# Omnetics_resistor_phantom.net
KiCad netlist of a schematic drawn in EAGLE
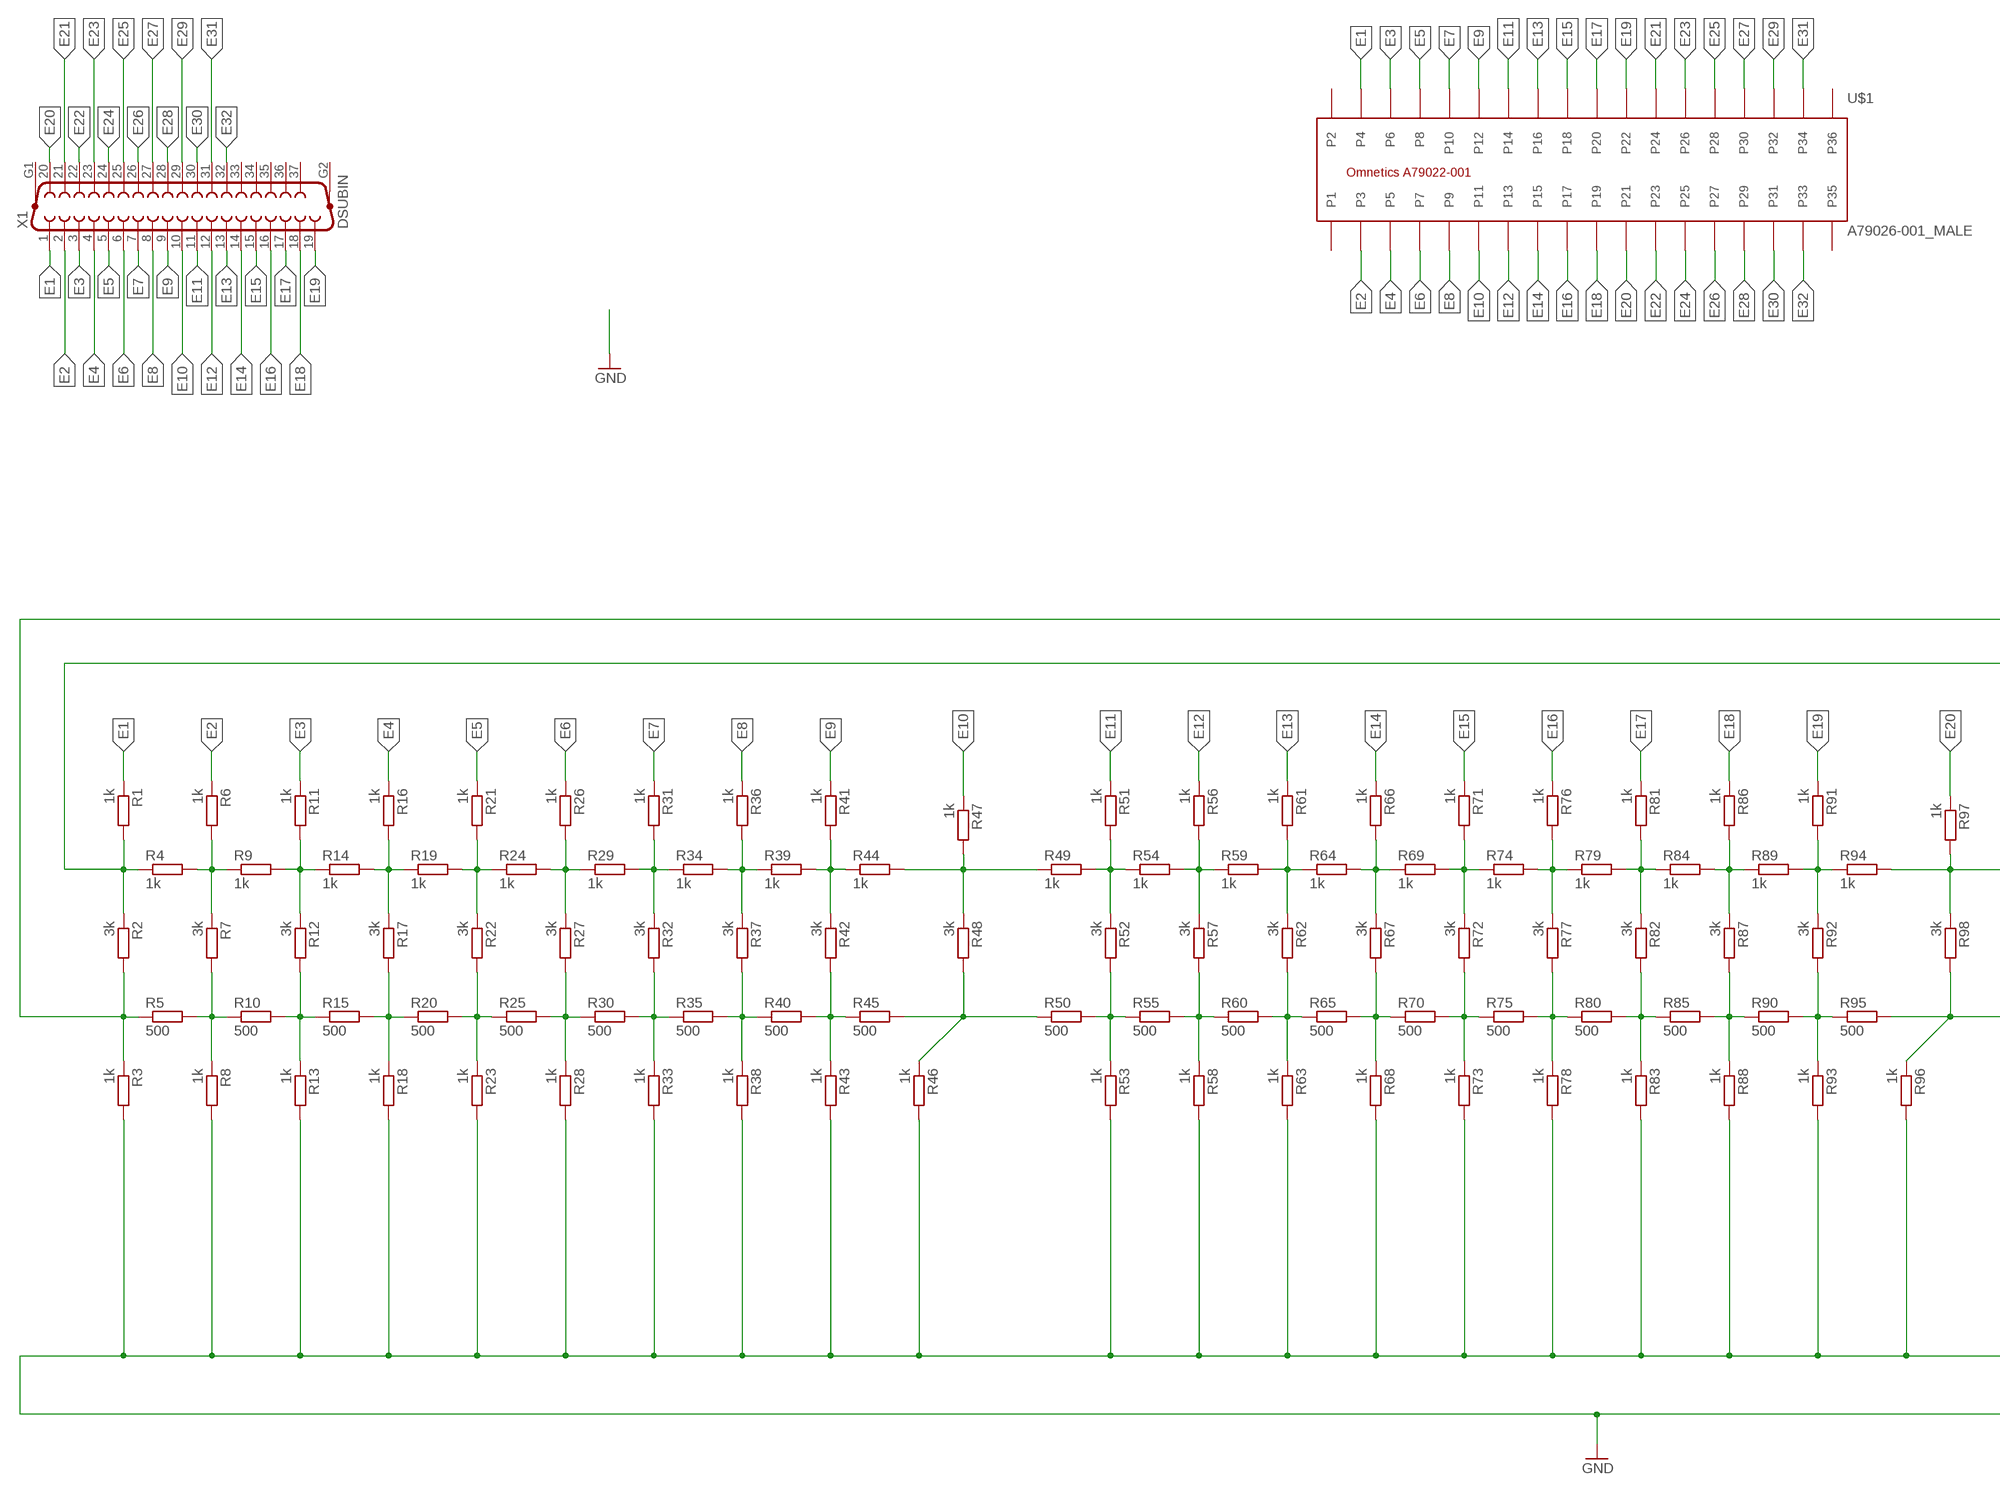
[diagram p0: schematic, sheet 1, part 1 of 2]
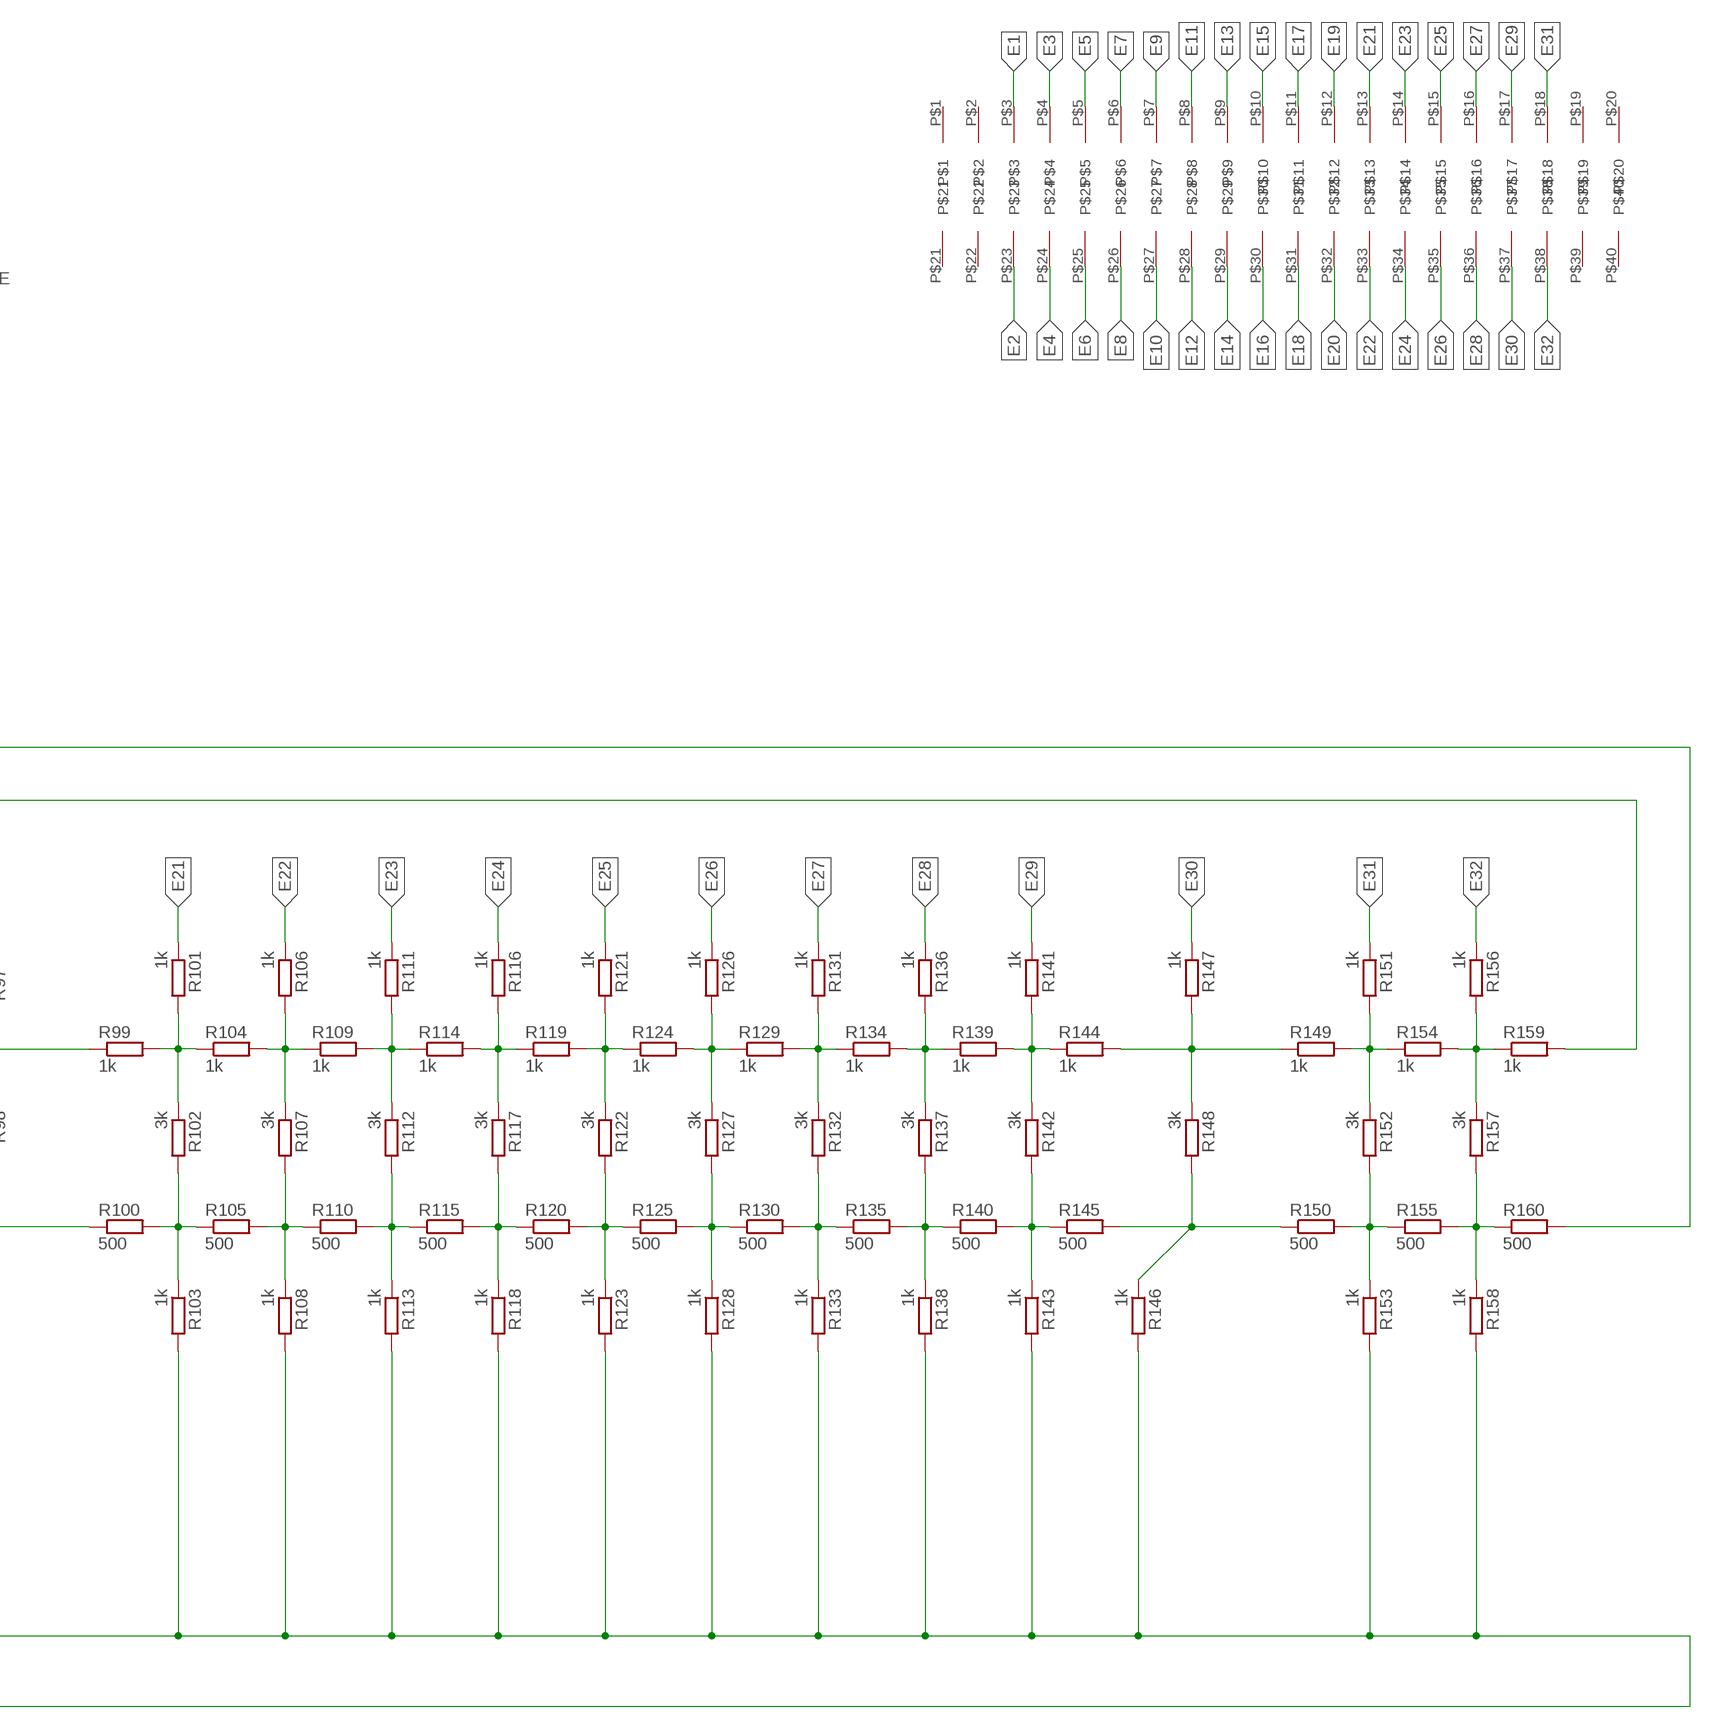
[diagram p1: schematic, sheet 1, part 2 of 2]

(export (version "E")
  (design (tool "Eeschema 10.0.6"))
  (components
    (comp (ref "R1")
      (value "1k")
      (footprint "eagle-import:R0402")
      (libsource (lib "eagle-import") (part "R-EU_R0402"))
    )
    (comp (ref "R2")
      (value "3k")
      (footprint "eagle-import:R0402")
      (libsource (lib "eagle-import") (part "R-EU_R0402"))
    )
    (comp (ref "R3")
      (value "1k")
      (footprint "eagle-import:R0402")
      (libsource (lib "eagle-import") (part "R-EU_R0402"))
    )
    (comp (ref "R4")
      (value "1k")
      (footprint "eagle-import:R0402")
      (libsource (lib "eagle-import") (part "R-EU_R0402"))
    )
    (comp (ref "R5")
      (value "500")
      (footprint "eagle-import:R0402")
      (libsource (lib "eagle-import") (part "R-EU_R0402"))
    )
    (comp (ref "R6")
      (value "1k")
      (footprint "eagle-import:R0402")
      (libsource (lib "eagle-import") (part "R-EU_R0402"))
    )
    (comp (ref "R7")
      (value "3k")
      (footprint "eagle-import:R0402")
      (libsource (lib "eagle-import") (part "R-EU_R0402"))
    )
    (comp (ref "R8")
      (value "1k")
      (footprint "eagle-import:R0402")
      (libsource (lib "eagle-import") (part "R-EU_R0402"))
    )
    (comp (ref "R9")
      (value "1k")
      (footprint "eagle-import:R0402")
      (libsource (lib "eagle-import") (part "R-EU_R0402"))
    )
    (comp (ref "R10")
      (value "500")
      (footprint "eagle-import:R0402")
      (libsource (lib "eagle-import") (part "R-EU_R0402"))
    )
    (comp (ref "R11")
      (value "1k")
      (footprint "eagle-import:R0402")
      (libsource (lib "eagle-import") (part "R-EU_R0402"))
    )
    (comp (ref "R12")
      (value "3k")
      (footprint "eagle-import:R0402")
      (libsource (lib "eagle-import") (part "R-EU_R0402"))
    )
    (comp (ref "R13")
      (value "1k")
      (footprint "eagle-import:R0402")
      (libsource (lib "eagle-import") (part "R-EU_R0402"))
    )
    (comp (ref "R14")
      (value "1k")
      (footprint "eagle-import:R0402")
      (libsource (lib "eagle-import") (part "R-EU_R0402"))
    )
    (comp (ref "R15")
      (value "500")
      (footprint "eagle-import:R0402")
      (libsource (lib "eagle-import") (part "R-EU_R0402"))
    )
    (comp (ref "R16")
      (value "1k")
      (footprint "eagle-import:R0402")
      (libsource (lib "eagle-import") (part "R-EU_R0402"))
    )
    (comp (ref "R17")
      (value "3k")
      (footprint "eagle-import:R0402")
      (libsource (lib "eagle-import") (part "R-EU_R0402"))
    )
    (comp (ref "R18")
      (value "1k")
      (footprint "eagle-import:R0402")
      (libsource (lib "eagle-import") (part "R-EU_R0402"))
    )
    (comp (ref "R19")
      (value "1k")
      (footprint "eagle-import:R0402")
      (libsource (lib "eagle-import") (part "R-EU_R0402"))
    )
    (comp (ref "R20")
      (value "500")
      (footprint "eagle-import:R0402")
      (libsource (lib "eagle-import") (part "R-EU_R0402"))
    )
    (comp (ref "R21")
      (value "1k")
      (footprint "eagle-import:R0402")
      (libsource (lib "eagle-import") (part "R-EU_R0402"))
    )
    (comp (ref "R22")
      (value "3k")
      (footprint "eagle-import:R0402")
      (libsource (lib "eagle-import") (part "R-EU_R0402"))
    )
    (comp (ref "R23")
      (value "1k")
      (footprint "eagle-import:R0402")
      (libsource (lib "eagle-import") (part "R-EU_R0402"))
    )
    (comp (ref "R24")
      (value "1k")
      (footprint "eagle-import:R0402")
      (libsource (lib "eagle-import") (part "R-EU_R0402"))
    )
    (comp (ref "R25")
      (value "500")
      (footprint "eagle-import:R0402")
      (libsource (lib "eagle-import") (part "R-EU_R0402"))
    )
    (comp (ref "R26")
      (value "1k")
      (footprint "eagle-import:R0402")
      (libsource (lib "eagle-import") (part "R-EU_R0402"))
    )
    (comp (ref "R27")
      (value "3k")
      (footprint "eagle-import:R0402")
      (libsource (lib "eagle-import") (part "R-EU_R0402"))
    )
    (comp (ref "R28")
      (value "1k")
      (footprint "eagle-import:R0402")
      (libsource (lib "eagle-import") (part "R-EU_R0402"))
    )
    (comp (ref "R29")
      (value "1k")
      (footprint "eagle-import:R0402")
      (libsource (lib "eagle-import") (part "R-EU_R0402"))
    )
    (comp (ref "R30")
      (value "500")
      (footprint "eagle-import:R0402")
      (libsource (lib "eagle-import") (part "R-EU_R0402"))
    )
    (comp (ref "R31")
      (value "1k")
      (footprint "eagle-import:R0402")
      (libsource (lib "eagle-import") (part "R-EU_R0402"))
    )
    (comp (ref "R32")
      (value "3k")
      (footprint "eagle-import:R0402")
      (libsource (lib "eagle-import") (part "R-EU_R0402"))
    )
    (comp (ref "R33")
      (value "1k")
      (footprint "eagle-import:R0402")
      (libsource (lib "eagle-import") (part "R-EU_R0402"))
    )
    (comp (ref "R34")
      (value "1k")
      (footprint "eagle-import:R0402")
      (libsource (lib "eagle-import") (part "R-EU_R0402"))
    )
    (comp (ref "R35")
      (value "500")
      (footprint "eagle-import:R0402")
      (libsource (lib "eagle-import") (part "R-EU_R0402"))
    )
    (comp (ref "R36")
      (value "1k")
      (footprint "eagle-import:R0402")
      (libsource (lib "eagle-import") (part "R-EU_R0402"))
    )
    (comp (ref "R37")
      (value "3k")
      (footprint "eagle-import:R0402")
      (libsource (lib "eagle-import") (part "R-EU_R0402"))
    )
    (comp (ref "R38")
      (value "1k")
      (footprint "eagle-import:R0402")
      (libsource (lib "eagle-import") (part "R-EU_R0402"))
    )
    (comp (ref "R39")
      (value "1k")
      (footprint "eagle-import:R0402")
      (libsource (lib "eagle-import") (part "R-EU_R0402"))
    )
    (comp (ref "R40")
      (value "500")
      (footprint "eagle-import:R0402")
      (libsource (lib "eagle-import") (part "R-EU_R0402"))
    )
    (comp (ref "R41")
      (value "1k")
      (footprint "eagle-import:R0402")
      (libsource (lib "eagle-import") (part "R-EU_R0402"))
    )
    (comp (ref "R42")
      (value "3k")
      (footprint "eagle-import:R0402")
      (libsource (lib "eagle-import") (part "R-EU_R0402"))
    )
    (comp (ref "R43")
      (value "1k")
      (footprint "eagle-import:R0402")
      (libsource (lib "eagle-import") (part "R-EU_R0402"))
    )
    (comp (ref "R44")
      (value "1k")
      (footprint "eagle-import:R0402")
      (libsource (lib "eagle-import") (part "R-EU_R0402"))
    )
    (comp (ref "R45")
      (value "500")
      (footprint "eagle-import:R0402")
      (libsource (lib "eagle-import") (part "R-EU_R0402"))
    )
    (comp (ref "R46")
      (value "1k")
      (footprint "eagle-import:R0402")
      (libsource (lib "eagle-import") (part "R-EU_R0402"))
    )
    (comp (ref "R47")
      (value "1k")
      (footprint "eagle-import:R0402")
      (libsource (lib "eagle-import") (part "R-EU_R0402"))
    )
    (comp (ref "R48")
      (value "3k")
      (footprint "eagle-import:R0402")
      (libsource (lib "eagle-import") (part "R-EU_R0402"))
    )
    (comp (ref "R49")
      (value "1k")
      (footprint "eagle-import:R0402")
      (libsource (lib "eagle-import") (part "R-EU_R0402"))
    )
    (comp (ref "R50")
      (value "500")
      (footprint "eagle-import:R0402")
      (libsource (lib "eagle-import") (part "R-EU_R0402"))
    )
    (comp (ref "R51")
      (value "1k")
      (footprint "eagle-import:R0402")
      (libsource (lib "eagle-import") (part "R-EU_R0402"))
    )
    (comp (ref "R52")
      (value "3k")
      (footprint "eagle-import:R0402")
      (libsource (lib "eagle-import") (part "R-EU_R0402"))
    )
    (comp (ref "R53")
      (value "1k")
      (footprint "eagle-import:R0402")
      (libsource (lib "eagle-import") (part "R-EU_R0402"))
    )
    (comp (ref "R54")
      (value "1k")
      (footprint "eagle-import:R0402")
      (libsource (lib "eagle-import") (part "R-EU_R0402"))
    )
    (comp (ref "R55")
      (value "500")
      (footprint "eagle-import:R0402")
      (libsource (lib "eagle-import") (part "R-EU_R0402"))
    )
    (comp (ref "R56")
      (value "1k")
      (footprint "eagle-import:R0402")
      (libsource (lib "eagle-import") (part "R-EU_R0402"))
    )
    (comp (ref "R57")
      (value "3k")
      (footprint "eagle-import:R0402")
      (libsource (lib "eagle-import") (part "R-EU_R0402"))
    )
    (comp (ref "R58")
      (value "1k")
      (footprint "eagle-import:R0402")
      (libsource (lib "eagle-import") (part "R-EU_R0402"))
    )
    (comp (ref "R59")
      (value "1k")
      (footprint "eagle-import:R0402")
      (libsource (lib "eagle-import") (part "R-EU_R0402"))
    )
    (comp (ref "R60")
      (value "500")
      (footprint "eagle-import:R0402")
      (libsource (lib "eagle-import") (part "R-EU_R0402"))
    )
    (comp (ref "R61")
      (value "1k")
      (footprint "eagle-import:R0402")
      (libsource (lib "eagle-import") (part "R-EU_R0402"))
    )
    (comp (ref "R62")
      (value "3k")
      (footprint "eagle-import:R0402")
      (libsource (lib "eagle-import") (part "R-EU_R0402"))
    )
    (comp (ref "R63")
      (value "1k")
      (footprint "eagle-import:R0402")
      (libsource (lib "eagle-import") (part "R-EU_R0402"))
    )
    (comp (ref "R64")
      (value "1k")
      (footprint "eagle-import:R0402")
      (libsource (lib "eagle-import") (part "R-EU_R0402"))
    )
    (comp (ref "R65")
      (value "500")
      (footprint "eagle-import:R0402")
      (libsource (lib "eagle-import") (part "R-EU_R0402"))
    )
    (comp (ref "R66")
      (value "1k")
      (footprint "eagle-import:R0402")
      (libsource (lib "eagle-import") (part "R-EU_R0402"))
    )
    (comp (ref "R67")
      (value "3k")
      (footprint "eagle-import:R0402")
      (libsource (lib "eagle-import") (part "R-EU_R0402"))
    )
    (comp (ref "R68")
      (value "1k")
      (footprint "eagle-import:R0402")
      (libsource (lib "eagle-import") (part "R-EU_R0402"))
    )
    (comp (ref "R69")
      (value "1k")
      (footprint "eagle-import:R0402")
      (libsource (lib "eagle-import") (part "R-EU_R0402"))
    )
    (comp (ref "R70")
      (value "500")
      (footprint "eagle-import:R0402")
      (libsource (lib "eagle-import") (part "R-EU_R0402"))
    )
    (comp (ref "R71")
      (value "1k")
      (footprint "eagle-import:R0402")
      (libsource (lib "eagle-import") (part "R-EU_R0402"))
    )
    (comp (ref "R72")
      (value "3k")
      (footprint "eagle-import:R0402")
      (libsource (lib "eagle-import") (part "R-EU_R0402"))
    )
    (comp (ref "R73")
      (value "1k")
      (footprint "eagle-import:R0402")
      (libsource (lib "eagle-import") (part "R-EU_R0402"))
    )
    (comp (ref "R74")
      (value "1k")
      (footprint "eagle-import:R0402")
      (libsource (lib "eagle-import") (part "R-EU_R0402"))
    )
    (comp (ref "R75")
      (value "500")
      (footprint "eagle-import:R0402")
      (libsource (lib "eagle-import") (part "R-EU_R0402"))
    )
    (comp (ref "R76")
      (value "1k")
      (footprint "eagle-import:R0402")
      (libsource (lib "eagle-import") (part "R-EU_R0402"))
    )
    (comp (ref "R77")
      (value "3k")
      (footprint "eagle-import:R0402")
      (libsource (lib "eagle-import") (part "R-EU_R0402"))
    )
    (comp (ref "R78")
      (value "1k")
      (footprint "eagle-import:R0402")
      (libsource (lib "eagle-import") (part "R-EU_R0402"))
    )
    (comp (ref "R79")
      (value "1k")
      (footprint "eagle-import:R0402")
      (libsource (lib "eagle-import") (part "R-EU_R0402"))
    )
    (comp (ref "R80")
      (value "500")
      (footprint "eagle-import:R0402")
      (libsource (lib "eagle-import") (part "R-EU_R0402"))
    )
    (comp (ref "R81")
      (value "1k")
      (footprint "eagle-import:R0402")
      (libsource (lib "eagle-import") (part "R-EU_R0402"))
    )
    (comp (ref "R82")
      (value "3k")
      (footprint "eagle-import:R0402")
      (libsource (lib "eagle-import") (part "R-EU_R0402"))
    )
    (comp (ref "R83")
      (value "1k")
      (footprint "eagle-import:R0402")
      (libsource (lib "eagle-import") (part "R-EU_R0402"))
    )
    (comp (ref "R84")
      (value "1k")
      (footprint "eagle-import:R0402")
      (libsource (lib "eagle-import") (part "R-EU_R0402"))
    )
    (comp (ref "R85")
      (value "500")
      (footprint "eagle-import:R0402")
      (libsource (lib "eagle-import") (part "R-EU_R0402"))
    )
    (comp (ref "R86")
      (value "1k")
      (footprint "eagle-import:R0402")
      (libsource (lib "eagle-import") (part "R-EU_R0402"))
    )
    (comp (ref "R87")
      (value "3k")
      (footprint "eagle-import:R0402")
      (libsource (lib "eagle-import") (part "R-EU_R0402"))
    )
    (comp (ref "R88")
      (value "1k")
      (footprint "eagle-import:R0402")
      (libsource (lib "eagle-import") (part "R-EU_R0402"))
    )
    (comp (ref "R89")
      (value "1k")
      (footprint "eagle-import:R0402")
      (libsource (lib "eagle-import") (part "R-EU_R0402"))
    )
    (comp (ref "R90")
      (value "500")
      (footprint "eagle-import:R0402")
      (libsource (lib "eagle-import") (part "R-EU_R0402"))
    )
    (comp (ref "R91")
      (value "1k")
      (footprint "eagle-import:R0402")
      (libsource (lib "eagle-import") (part "R-EU_R0402"))
    )
    (comp (ref "R92")
      (value "3k")
      (footprint "eagle-import:R0402")
      (libsource (lib "eagle-import") (part "R-EU_R0402"))
    )
    (comp (ref "R93")
      (value "1k")
      (footprint "eagle-import:R0402")
      (libsource (lib "eagle-import") (part "R-EU_R0402"))
    )
    (comp (ref "R94")
      (value "1k")
      (footprint "eagle-import:R0402")
      (libsource (lib "eagle-import") (part "R-EU_R0402"))
    )
    (comp (ref "R95")
      (value "500")
      (footprint "eagle-import:R0402")
      (libsource (lib "eagle-import") (part "R-EU_R0402"))
    )
    (comp (ref "R96")
      (value "1k")
      (footprint "eagle-import:R0402")
      (libsource (lib "eagle-import") (part "R-EU_R0402"))
    )
    (comp (ref "R97")
      (value "1k")
      (footprint "eagle-import:R0402")
      (libsource (lib "eagle-import") (part "R-EU_R0402"))
    )
    (comp (ref "R98")
      (value "3k")
      (footprint "eagle-import:R0402")
      (libsource (lib "eagle-import") (part "R-EU_R0402"))
    )
    (comp (ref "R99")
      (value "1k")
      (footprint "eagle-import:R0402")
      (libsource (lib "eagle-import") (part "R-EU_R0402"))
    )
    (comp (ref "R100")
      (value "500")
      (footprint "eagle-import:R0402")
      (libsource (lib "eagle-import") (part "R-EU_R0402"))
    )
    (comp (ref "R101")
      (value "1k")
      (footprint "eagle-import:R0402")
      (libsource (lib "eagle-import") (part "R-EU_R0402"))
    )
    (comp (ref "R102")
      (value "3k")
      (footprint "eagle-import:R0402")
      (libsource (lib "eagle-import") (part "R-EU_R0402"))
    )
    (comp (ref "R103")
      (value "1k")
      (footprint "eagle-import:R0402")
      (libsource (lib "eagle-import") (part "R-EU_R0402"))
    )
    (comp (ref "R104")
      (value "1k")
      (footprint "eagle-import:R0402")
      (libsource (lib "eagle-import") (part "R-EU_R0402"))
    )
    (comp (ref "R105")
      (value "500")
      (footprint "eagle-import:R0402")
      (libsource (lib "eagle-import") (part "R-EU_R0402"))
    )
    (comp (ref "R106")
      (value "1k")
      (footprint "eagle-import:R0402")
      (libsource (lib "eagle-import") (part "R-EU_R0402"))
    )
    (comp (ref "R107")
      (value "3k")
      (footprint "eagle-import:R0402")
      (libsource (lib "eagle-import") (part "R-EU_R0402"))
    )
    (comp (ref "R108")
      (value "1k")
      (footprint "eagle-import:R0402")
      (libsource (lib "eagle-import") (part "R-EU_R0402"))
    )
    (comp (ref "R109")
      (value "1k")
      (footprint "eagle-import:R0402")
      (libsource (lib "eagle-import") (part "R-EU_R0402"))
    )
    (comp (ref "R110")
      (value "500")
      (footprint "eagle-import:R0402")
      (libsource (lib "eagle-import") (part "R-EU_R0402"))
    )
    (comp (ref "R111")
      (value "1k")
      (footprint "eagle-import:R0402")
      (libsource (lib "eagle-import") (part "R-EU_R0402"))
    )
    (comp (ref "R112")
      (value "3k")
      (footprint "eagle-import:R0402")
      (libsource (lib "eagle-import") (part "R-EU_R0402"))
    )
    (comp (ref "R113")
      (value "1k")
      (footprint "eagle-import:R0402")
      (libsource (lib "eagle-import") (part "R-EU_R0402"))
    )
    (comp (ref "R114")
      (value "1k")
      (footprint "eagle-import:R0402")
      (libsource (lib "eagle-import") (part "R-EU_R0402"))
    )
    (comp (ref "R115")
      (value "500")
      (footprint "eagle-import:R0402")
      (libsource (lib "eagle-import") (part "R-EU_R0402"))
    )
    (comp (ref "R116")
      (value "1k")
      (footprint "eagle-import:R0402")
      (libsource (lib "eagle-import") (part "R-EU_R0402"))
    )
    (comp (ref "R117")
      (value "3k")
      (footprint "eagle-import:R0402")
      (libsource (lib "eagle-import") (part "R-EU_R0402"))
    )
    (comp (ref "R118")
      (value "1k")
      (footprint "eagle-import:R0402")
      (libsource (lib "eagle-import") (part "R-EU_R0402"))
    )
    (comp (ref "R119")
      (value "1k")
      (footprint "eagle-import:R0402")
      (libsource (lib "eagle-import") (part "R-EU_R0402"))
    )
    (comp (ref "R120")
      (value "500")
      (footprint "eagle-import:R0402")
      (libsource (lib "eagle-import") (part "R-EU_R0402"))
    )
    (comp (ref "R121")
      (value "1k")
      (footprint "eagle-import:R0402")
      (libsource (lib "eagle-import") (part "R-EU_R0402"))
    )
    (comp (ref "R122")
      (value "3k")
      (footprint "eagle-import:R0402")
      (libsource (lib "eagle-import") (part "R-EU_R0402"))
    )
    (comp (ref "R123")
      (value "1k")
      (footprint "eagle-import:R0402")
      (libsource (lib "eagle-import") (part "R-EU_R0402"))
    )
    (comp (ref "R124")
      (value "1k")
      (footprint "eagle-import:R0402")
      (libsource (lib "eagle-import") (part "R-EU_R0402"))
    )
    (comp (ref "R125")
      (value "500")
      (footprint "eagle-import:R0402")
      (libsource (lib "eagle-import") (part "R-EU_R0402"))
    )
    (comp (ref "R126")
      (value "1k")
      (footprint "eagle-import:R0402")
      (libsource (lib "eagle-import") (part "R-EU_R0402"))
    )
    (comp (ref "R127")
      (value "3k")
      (footprint "eagle-import:R0402")
      (libsource (lib "eagle-import") (part "R-EU_R0402"))
    )
    (comp (ref "R128")
      (value "1k")
      (footprint "eagle-import:R0402")
      (libsource (lib "eagle-import") (part "R-EU_R0402"))
    )
    (comp (ref "R129")
      (value "1k")
      (footprint "eagle-import:R0402")
      (libsource (lib "eagle-import") (part "R-EU_R0402"))
    )
    (comp (ref "R130")
      (value "500")
      (footprint "eagle-import:R0402")
      (libsource (lib "eagle-import") (part "R-EU_R0402"))
    )
    (comp (ref "R131")
      (value "1k")
      (footprint "eagle-import:R0402")
      (libsource (lib "eagle-import") (part "R-EU_R0402"))
    )
    (comp (ref "R132")
      (value "3k")
      (footprint "eagle-import:R0402")
      (libsource (lib "eagle-import") (part "R-EU_R0402"))
    )
    (comp (ref "R133")
      (value "1k")
      (footprint "eagle-import:R0402")
      (libsource (lib "eagle-import") (part "R-EU_R0402"))
    )
    (comp (ref "R134")
      (value "1k")
      (footprint "eagle-import:R0402")
      (libsource (lib "eagle-import") (part "R-EU_R0402"))
    )
    (comp (ref "R135")
      (value "500")
      (footprint "eagle-import:R0402")
      (libsource (lib "eagle-import") (part "R-EU_R0402"))
    )
    (comp (ref "R136")
      (value "1k")
      (footprint "eagle-import:R0402")
      (libsource (lib "eagle-import") (part "R-EU_R0402"))
    )
    (comp (ref "R137")
      (value "3k")
      (footprint "eagle-import:R0402")
      (libsource (lib "eagle-import") (part "R-EU_R0402"))
    )
    (comp (ref "R138")
      (value "1k")
      (footprint "eagle-import:R0402")
      (libsource (lib "eagle-import") (part "R-EU_R0402"))
    )
    (comp (ref "R139")
      (value "1k")
      (footprint "eagle-import:R0402")
      (libsource (lib "eagle-import") (part "R-EU_R0402"))
    )
    (comp (ref "R140")
      (value "500")
      (footprint "eagle-import:R0402")
      (libsource (lib "eagle-import") (part "R-EU_R0402"))
    )
    (comp (ref "R141")
      (value "1k")
      (footprint "eagle-import:R0402")
      (libsource (lib "eagle-import") (part "R-EU_R0402"))
    )
    (comp (ref "R142")
      (value "3k")
      (footprint "eagle-import:R0402")
      (libsource (lib "eagle-import") (part "R-EU_R0402"))
    )
    (comp (ref "R143")
      (value "1k")
      (footprint "eagle-import:R0402")
      (libsource (lib "eagle-import") (part "R-EU_R0402"))
    )
    (comp (ref "R144")
      (value "1k")
      (footprint "eagle-import:R0402")
      (libsource (lib "eagle-import") (part "R-EU_R0402"))
    )
    (comp (ref "R145")
      (value "500")
      (footprint "eagle-import:R0402")
      (libsource (lib "eagle-import") (part "R-EU_R0402"))
    )
    (comp (ref "R146")
      (value "1k")
      (footprint "eagle-import:R0402")
      (libsource (lib "eagle-import") (part "R-EU_R0402"))
    )
    (comp (ref "R147")
      (value "1k")
      (footprint "eagle-import:R0402")
      (libsource (lib "eagle-import") (part "R-EU_R0402"))
    )
    (comp (ref "R148")
      (value "3k")
      (footprint "eagle-import:R0402")
      (libsource (lib "eagle-import") (part "R-EU_R0402"))
    )
    (comp (ref "R149")
      (value "1k")
      (footprint "eagle-import:R0402")
      (libsource (lib "eagle-import") (part "R-EU_R0402"))
    )
    (comp (ref "R150")
      (value "500")
      (footprint "eagle-import:R0402")
      (libsource (lib "eagle-import") (part "R-EU_R0402"))
    )
    (comp (ref "R151")
      (value "1k")
      (footprint "eagle-import:R0402")
      (libsource (lib "eagle-import") (part "R-EU_R0402"))
    )
    (comp (ref "R152")
      (value "3k")
      (footprint "eagle-import:R0402")
      (libsource (lib "eagle-import") (part "R-EU_R0402"))
    )
    (comp (ref "R153")
      (value "1k")
      (footprint "eagle-import:R0402")
      (libsource (lib "eagle-import") (part "R-EU_R0402"))
    )
    (comp (ref "R154")
      (value "1k")
      (footprint "eagle-import:R0402")
      (libsource (lib "eagle-import") (part "R-EU_R0402"))
    )
    (comp (ref "R155")
      (value "500")
      (footprint "eagle-import:R0402")
      (libsource (lib "eagle-import") (part "R-EU_R0402"))
    )
    (comp (ref "R156")
      (value "1k")
      (footprint "eagle-import:R0402")
      (libsource (lib "eagle-import") (part "R-EU_R0402"))
    )
    (comp (ref "R157")
      (value "3k")
      (footprint "eagle-import:R0402")
      (libsource (lib "eagle-import") (part "R-EU_R0402"))
    )
    (comp (ref "R158")
      (value "1k")
      (footprint "eagle-import:R0402")
      (libsource (lib "eagle-import") (part "R-EU_R0402"))
    )
    (comp (ref "R159")
      (value "1k")
      (footprint "eagle-import:R0402")
      (libsource (lib "eagle-import") (part "R-EU_R0402"))
    )
    (comp (ref "R160")
      (value "500")
      (footprint "eagle-import:R0402")
      (libsource (lib "eagle-import") (part "R-EU_R0402"))
    )
    (comp (ref "U$1")
      (value "A79026-001_MALE")
      (footprint "eagle-import:A79026-001_MALE")
      (libsource (lib "eagle-import") (part "A79026-001_MALE"))
    )
    (comp (ref "U$2")
      (value "SAMTEC_FTSH_LARGEPAD")
      (footprint "eagle-import:SAMTEC-FTSH-LARGEPAD")
      (libsource (lib "eagle-import") (part "SAMTEC_FTSH_LARGEPAD"))
    )
    (comp (ref "X1")
      (value "DSUBIN")
      (footprint "eagle-import:F37VP")
      (libsource (lib "eagle-import") (part "F37VP"))
    )
  )
  (nets
    (net (code "1") (name "E1") (class "Default")
      (node (ref "R1") (pin "1") (pinfunction "1_1") (pintype "passive"))
      (node (ref "U$1") (pin "P4") (pinfunction "P4_P4") (pintype "bidirectional"))
      (node (ref "U$2") (pin "P$3") (pinfunction "P$3_P$3") (pintype "bidirectional"))
      (node (ref "X1") (pin "1") (pinfunction "1_1") (pintype "passive"))
    )
    (net (code "2") (name "E2") (class "Default")
      (node (ref "R6") (pin "1") (pinfunction "1_1") (pintype "passive"))
      (node (ref "U$1") (pin "P3") (pinfunction "P3_P3") (pintype "bidirectional"))
      (node (ref "U$2") (pin "P$23") (pinfunction "P$23_P$23") (pintype "bidirectional"))
      (node (ref "X1") (pin "2") (pinfunction "2_2") (pintype "passive"))
    )
    (net (code "3") (name "E3") (class "Default")
      (node (ref "R11") (pin "1") (pinfunction "1_1") (pintype "passive"))
      (node (ref "U$1") (pin "P6") (pinfunction "P6_P6") (pintype "bidirectional"))
      (node (ref "U$2") (pin "P$4") (pinfunction "P$4_P$4") (pintype "bidirectional"))
      (node (ref "X1") (pin "3") (pinfunction "3_3") (pintype "passive"))
    )
    (net (code "4") (name "E4") (class "Default")
      (node (ref "R16") (pin "1") (pinfunction "1_1") (pintype "passive"))
      (node (ref "U$1") (pin "P5") (pinfunction "P5_P5") (pintype "bidirectional"))
      (node (ref "U$2") (pin "P$24") (pinfunction "P$24_P$24") (pintype "bidirectional"))
      (node (ref "X1") (pin "4") (pinfunction "4_4") (pintype "passive"))
    )
    (net (code "5") (name "E5") (class "Default")
      (node (ref "R21") (pin "1") (pinfunction "1_1") (pintype "passive"))
      (node (ref "U$1") (pin "P8") (pinfunction "P8_P8") (pintype "bidirectional"))
      (node (ref "U$2") (pin "P$5") (pinfunction "P$5_P$5") (pintype "bidirectional"))
      (node (ref "X1") (pin "5") (pinfunction "5_5") (pintype "passive"))
    )
    (net (code "6") (name "E6") (class "Default")
      (node (ref "R26") (pin "1") (pinfunction "1_1") (pintype "passive"))
      (node (ref "U$1") (pin "P7") (pinfunction "P7_P7") (pintype "bidirectional"))
      (node (ref "U$2") (pin "P$25") (pinfunction "P$25_P$25") (pintype "bidirectional"))
      (node (ref "X1") (pin "6") (pinfunction "6_6") (pintype "passive"))
    )
    (net (code "7") (name "E7") (class "Default")
      (node (ref "R31") (pin "1") (pinfunction "1_1") (pintype "passive"))
      (node (ref "U$1") (pin "P10") (pinfunction "P10_P10") (pintype "bidirectional"))
      (node (ref "U$2") (pin "P$6") (pinfunction "P$6_P$6") (pintype "bidirectional"))
      (node (ref "X1") (pin "7") (pinfunction "7_7") (pintype "passive"))
    )
    (net (code "8") (name "E8") (class "Default")
      (node (ref "R36") (pin "1") (pinfunction "1_1") (pintype "passive"))
      (node (ref "U$1") (pin "P9") (pinfunction "P9_P9") (pintype "bidirectional"))
      (node (ref "U$2") (pin "P$26") (pinfunction "P$26_P$26") (pintype "bidirectional"))
      (node (ref "X1") (pin "8") (pinfunction "8_8") (pintype "passive"))
    )
    (net (code "9") (name "E9") (class "Default")
      (node (ref "R41") (pin "1") (pinfunction "1_1") (pintype "passive"))
      (node (ref "U$1") (pin "P12") (pinfunction "P12_P12") (pintype "bidirectional"))
      (node (ref "U$2") (pin "P$7") (pinfunction "P$7_P$7") (pintype "bidirectional"))
      (node (ref "X1") (pin "9") (pinfunction "9_9") (pintype "passive"))
    )
    (net (code "10") (name "E10") (class "Default")
      (node (ref "R47") (pin "1") (pinfunction "1_1") (pintype "passive"))
      (node (ref "U$1") (pin "P11") (pinfunction "P11_P11") (pintype "bidirectional"))
      (node (ref "U$2") (pin "P$27") (pinfunction "P$27_P$27") (pintype "bidirectional"))
      (node (ref "X1") (pin "10") (pinfunction "10_10") (pintype "passive"))
    )
    (net (code "11") (name "E11") (class "Default")
      (node (ref "R51") (pin "1") (pinfunction "1_1") (pintype "passive"))
      (node (ref "U$1") (pin "P14") (pinfunction "P14_P14") (pintype "bidirectional"))
      (node (ref "U$2") (pin "P$8") (pinfunction "P$8_P$8") (pintype "bidirectional"))
      (node (ref "X1") (pin "11") (pinfunction "11_11") (pintype "passive"))
    )
    (net (code "12") (name "E12") (class "Default")
      (node (ref "R56") (pin "1") (pinfunction "1_1") (pintype "passive"))
      (node (ref "U$1") (pin "P13") (pinfunction "P13_P13") (pintype "bidirectional"))
      (node (ref "U$2") (pin "P$28") (pinfunction "P$28_P$28") (pintype "bidirectional"))
      (node (ref "X1") (pin "12") (pinfunction "12_12") (pintype "passive"))
    )
    (net (code "13") (name "E13") (class "Default")
      (node (ref "R61") (pin "1") (pinfunction "1_1") (pintype "passive"))
      (node (ref "U$1") (pin "P16") (pinfunction "P16_P16") (pintype "bidirectional"))
      (node (ref "U$2") (pin "P$9") (pinfunction "P$9_P$9") (pintype "bidirectional"))
      (node (ref "X1") (pin "13") (pinfunction "13_13") (pintype "passive"))
    )
    (net (code "14") (name "E14") (class "Default")
      (node (ref "R66") (pin "1") (pinfunction "1_1") (pintype "passive"))
      (node (ref "U$1") (pin "P15") (pinfunction "P15_P15") (pintype "bidirectional"))
      (node (ref "U$2") (pin "P$29") (pinfunction "P$29_P$29") (pintype "bidirectional"))
      (node (ref "X1") (pin "14") (pinfunction "14_14") (pintype "passive"))
    )
    (net (code "15") (name "E15") (class "Default")
      (node (ref "R71") (pin "1") (pinfunction "1_1") (pintype "passive"))
      (node (ref "U$1") (pin "P18") (pinfunction "P18_P18") (pintype "bidirectional"))
      (node (ref "U$2") (pin "P$10") (pinfunction "P$10_P$10") (pintype "bidirectional"))
      (node (ref "X1") (pin "15") (pinfunction "15_15") (pintype "passive"))
    )
    (net (code "16") (name "E16") (class "Default")
      (node (ref "R76") (pin "1") (pinfunction "1_1") (pintype "passive"))
      (node (ref "U$1") (pin "P17") (pinfunction "P17_P17") (pintype "bidirectional"))
      (node (ref "U$2") (pin "P$30") (pinfunction "P$30_P$30") (pintype "bidirectional"))
      (node (ref "X1") (pin "16") (pinfunction "16_16") (pintype "passive"))
    )
    (net (code "17") (name "E17") (class "Default")
      (node (ref "R81") (pin "1") (pinfunction "1_1") (pintype "passive"))
      (node (ref "U$1") (pin "P20") (pinfunction "P20_P20") (pintype "bidirectional"))
      (node (ref "U$2") (pin "P$11") (pinfunction "P$11_P$11") (pintype "bidirectional"))
      (node (ref "X1") (pin "17") (pinfunction "17_17") (pintype "passive"))
    )
    (net (code "18") (name "E18") (class "Default")
      (node (ref "R86") (pin "1") (pinfunction "1_1") (pintype "passive"))
      (node (ref "U$1") (pin "P19") (pinfunction "P19_P19") (pintype "bidirectional"))
      (node (ref "U$2") (pin "P$31") (pinfunction "P$31_P$31") (pintype "bidirectional"))
      (node (ref "X1") (pin "18") (pinfunction "18_18") (pintype "passive"))
    )
    (net (code "19") (name "E19") (class "Default")
      (node (ref "R91") (pin "1") (pinfunction "1_1") (pintype "passive"))
      (node (ref "U$1") (pin "P22") (pinfunction "P22_P22") (pintype "bidirectional"))
      (node (ref "U$2") (pin "P$12") (pinfunction "P$12_P$12") (pintype "bidirectional"))
      (node (ref "X1") (pin "19") (pinfunction "19_19") (pintype "passive"))
    )
    (net (code "20") (name "E20") (class "Default")
      (node (ref "R97") (pin "1") (pinfunction "1_1") (pintype "passive"))
      (node (ref "U$1") (pin "P21") (pinfunction "P21_P21") (pintype "bidirectional"))
      (node (ref "U$2") (pin "P$32") (pinfunction "P$32_P$32") (pintype "bidirectional"))
      (node (ref "X1") (pin "20") (pinfunction "20_20") (pintype "passive"))
    )
    (net (code "21") (name "E21") (class "Default")
      (node (ref "R101") (pin "1") (pinfunction "1_1") (pintype "passive"))
      (node (ref "U$1") (pin "P24") (pinfunction "P24_P24") (pintype "bidirectional"))
      (node (ref "U$2") (pin "P$13") (pinfunction "P$13_P$13") (pintype "bidirectional"))
      (node (ref "X1") (pin "21") (pinfunction "21_21") (pintype "passive"))
    )
    (net (code "22") (name "E22") (class "Default")
      (node (ref "R106") (pin "1") (pinfunction "1_1") (pintype "passive"))
      (node (ref "U$1") (pin "P23") (pinfunction "P23_P23") (pintype "bidirectional"))
      (node (ref "U$2") (pin "P$33") (pinfunction "P$33_P$33") (pintype "bidirectional"))
      (node (ref "X1") (pin "22") (pinfunction "22_22") (pintype "passive"))
    )
    (net (code "23") (name "E23") (class "Default")
      (node (ref "R111") (pin "1") (pinfunction "1_1") (pintype "passive"))
      (node (ref "U$1") (pin "P26") (pinfunction "P26_P26") (pintype "bidirectional"))
      (node (ref "U$2") (pin "P$14") (pinfunction "P$14_P$14") (pintype "bidirectional"))
      (node (ref "X1") (pin "23") (pinfunction "23_23") (pintype "passive"))
    )
    (net (code "24") (name "E24") (class "Default")
      (node (ref "R116") (pin "1") (pinfunction "1_1") (pintype "passive"))
      (node (ref "U$1") (pin "P25") (pinfunction "P25_P25") (pintype "bidirectional"))
      (node (ref "U$2") (pin "P$34") (pinfunction "P$34_P$34") (pintype "bidirectional"))
      (node (ref "X1") (pin "24") (pinfunction "24_24") (pintype "passive"))
    )
    (net (code "25") (name "E25") (class "Default")
      (node (ref "R121") (pin "1") (pinfunction "1_1") (pintype "passive"))
      (node (ref "U$1") (pin "P28") (pinfunction "P28_P28") (pintype "bidirectional"))
      (node (ref "U$2") (pin "P$15") (pinfunction "P$15_P$15") (pintype "bidirectional"))
      (node (ref "X1") (pin "25") (pinfunction "25_25") (pintype "passive"))
    )
    (net (code "26") (name "E26") (class "Default")
      (node (ref "R126") (pin "1") (pinfunction "1_1") (pintype "passive"))
      (node (ref "U$1") (pin "P27") (pinfunction "P27_P27") (pintype "bidirectional"))
      (node (ref "U$2") (pin "P$35") (pinfunction "P$35_P$35") (pintype "bidirectional"))
      (node (ref "X1") (pin "26") (pinfunction "26_26") (pintype "passive"))
    )
    (net (code "27") (name "E27") (class "Default")
      (node (ref "R131") (pin "1") (pinfunction "1_1") (pintype "passive"))
      (node (ref "U$1") (pin "P30") (pinfunction "P30_P30") (pintype "bidirectional"))
      (node (ref "U$2") (pin "P$16") (pinfunction "P$16_P$16") (pintype "bidirectional"))
      (node (ref "X1") (pin "27") (pinfunction "27_27") (pintype "passive"))
    )
    (net (code "28") (name "E28") (class "Default")
      (node (ref "R136") (pin "1") (pinfunction "1_1") (pintype "passive"))
      (node (ref "U$1") (pin "P29") (pinfunction "P29_P29") (pintype "bidirectional"))
      (node (ref "U$2") (pin "P$36") (pinfunction "P$36_P$36") (pintype "bidirectional"))
      (node (ref "X1") (pin "28") (pinfunction "28_28") (pintype "passive"))
    )
    (net (code "29") (name "E29") (class "Default")
      (node (ref "R141") (pin "1") (pinfunction "1_1") (pintype "passive"))
      (node (ref "U$1") (pin "P32") (pinfunction "P32_P32") (pintype "bidirectional"))
      (node (ref "U$2") (pin "P$17") (pinfunction "P$17_P$17") (pintype "bidirectional"))
      (node (ref "X1") (pin "29") (pinfunction "29_29") (pintype "passive"))
    )
    (net (code "30") (name "E30") (class "Default")
      (node (ref "R147") (pin "1") (pinfunction "1_1") (pintype "passive"))
      (node (ref "U$1") (pin "P31") (pinfunction "P31_P31") (pintype "bidirectional"))
      (node (ref "U$2") (pin "P$37") (pinfunction "P$37_P$37") (pintype "bidirectional"))
      (node (ref "X1") (pin "30") (pinfunction "30_30") (pintype "passive"))
    )
    (net (code "31") (name "E31") (class "Default")
      (node (ref "R151") (pin "1") (pinfunction "1_1") (pintype "passive"))
      (node (ref "U$1") (pin "P34") (pinfunction "P34_P34") (pintype "bidirectional"))
      (node (ref "U$2") (pin "P$18") (pinfunction "P$18_P$18") (pintype "bidirectional"))
      (node (ref "X1") (pin "31") (pinfunction "31_31") (pintype "passive"))
    )
    (net (code "32") (name "E32") (class "Default")
      (node (ref "R156") (pin "1") (pinfunction "1_1") (pintype "passive"))
      (node (ref "U$1") (pin "P33") (pinfunction "P33_P33") (pintype "bidirectional"))
      (node (ref "U$2") (pin "P$38") (pinfunction "P$38_P$38") (pintype "bidirectional"))
      (node (ref "X1") (pin "32") (pinfunction "32_32") (pintype "passive"))
    )
    (net (code "33") (name "GND") (class "Default")
      (node (ref "R103") (pin "2") (pinfunction "2_2") (pintype "passive"))
      (node (ref "R108") (pin "2") (pinfunction "2_2") (pintype "passive"))
      (node (ref "R113") (pin "2") (pinfunction "2_2") (pintype "passive"))
      (node (ref "R118") (pin "2") (pinfunction "2_2") (pintype "passive"))
      (node (ref "R123") (pin "2") (pinfunction "2_2") (pintype "passive"))
      (node (ref "R128") (pin "2") (pinfunction "2_2") (pintype "passive"))
      (node (ref "R13") (pin "2") (pinfunction "2_2") (pintype "passive"))
      (node (ref "R133") (pin "2") (pinfunction "2_2") (pintype "passive"))
      (node (ref "R138") (pin "2") (pinfunction "2_2") (pintype "passive"))
      (node (ref "R143") (pin "2") (pinfunction "2_2") (pintype "passive"))
      (node (ref "R146") (pin "2") (pinfunction "2_2") (pintype "passive"))
      (node (ref "R153") (pin "2") (pinfunction "2_2") (pintype "passive"))
      (node (ref "R158") (pin "2") (pinfunction "2_2") (pintype "passive"))
      (node (ref "R18") (pin "2") (pinfunction "2_2") (pintype "passive"))
      (node (ref "R23") (pin "2") (pinfunction "2_2") (pintype "passive"))
      (node (ref "R28") (pin "2") (pinfunction "2_2") (pintype "passive"))
      (node (ref "R3") (pin "2") (pinfunction "2_2") (pintype "passive"))
      (node (ref "R33") (pin "2") (pinfunction "2_2") (pintype "passive"))
      (node (ref "R38") (pin "2") (pinfunction "2_2") (pintype "passive"))
      (node (ref "R43") (pin "2") (pinfunction "2_2") (pintype "passive"))
      (node (ref "R46") (pin "2") (pinfunction "2_2") (pintype "passive"))
      (node (ref "R53") (pin "2") (pinfunction "2_2") (pintype "passive"))
      (node (ref "R58") (pin "2") (pinfunction "2_2") (pintype "passive"))
      (node (ref "R63") (pin "2") (pinfunction "2_2") (pintype "passive"))
      (node (ref "R68") (pin "2") (pinfunction "2_2") (pintype "passive"))
      (node (ref "R73") (pin "2") (pinfunction "2_2") (pintype "passive"))
      (node (ref "R78") (pin "2") (pinfunction "2_2") (pintype "passive"))
      (node (ref "R8") (pin "2") (pinfunction "2_2") (pintype "passive"))
      (node (ref "R83") (pin "2") (pinfunction "2_2") (pintype "passive"))
      (node (ref "R88") (pin "2") (pinfunction "2_2") (pintype "passive"))
      (node (ref "R93") (pin "2") (pinfunction "2_2") (pintype "passive"))
      (node (ref "R96") (pin "2") (pinfunction "2_2") (pintype "passive"))
    )
    (net (code "34") (name "Net-(R1-Pad2)") (class "Default")
      (node (ref "R1") (pin "2") (pinfunction "2_2") (pintype "passive"))
      (node (ref "R159") (pin "2") (pinfunction "2_2") (pintype "passive"))
      (node (ref "R2") (pin "1") (pinfunction "1_1") (pintype "passive"))
      (node (ref "R4") (pin "1") (pinfunction "1_1") (pintype "passive"))
    )
    (net (code "35") (name "Net-(R4-Pad2)") (class "Default")
      (node (ref "R4") (pin "2") (pinfunction "2_2") (pintype "passive"))
      (node (ref "R6") (pin "2") (pinfunction "2_2") (pintype "passive"))
      (node (ref "R7") (pin "1") (pinfunction "1_1") (pintype "passive"))
      (node (ref "R9") (pin "1") (pinfunction "1_1") (pintype "passive"))
    )
    (net (code "36") (name "Net-(R10-Pad1)") (class "Default")
      (node (ref "R10") (pin "1") (pinfunction "1_1") (pintype "passive"))
      (node (ref "R5") (pin "2") (pinfunction "2_2") (pintype "passive"))
      (node (ref "R7") (pin "2") (pinfunction "2_2") (pintype "passive"))
      (node (ref "R8") (pin "1") (pinfunction "1_1") (pintype "passive"))
    )
    (net (code "37") (name "Net-(R10-Pad2)") (class "Default")
      (node (ref "R10") (pin "2") (pinfunction "2_2") (pintype "passive"))
      (node (ref "R12") (pin "2") (pinfunction "2_2") (pintype "passive"))
      (node (ref "R13") (pin "1") (pinfunction "1_1") (pintype "passive"))
      (node (ref "R15") (pin "1") (pinfunction "1_1") (pintype "passive"))
    )
    (net (code "38") (name "Net-(R11-Pad2)") (class "Default")
      (node (ref "R11") (pin "2") (pinfunction "2_2") (pintype "passive"))
      (node (ref "R12") (pin "1") (pinfunction "1_1") (pintype "passive"))
      (node (ref "R14") (pin "1") (pinfunction "1_1") (pintype "passive"))
      (node (ref "R9") (pin "2") (pinfunction "2_2") (pintype "passive"))
    )
    (net (code "39") (name "Net-(R14-Pad2)") (class "Default")
      (node (ref "R14") (pin "2") (pinfunction "2_2") (pintype "passive"))
      (node (ref "R16") (pin "2") (pinfunction "2_2") (pintype "passive"))
      (node (ref "R17") (pin "1") (pinfunction "1_1") (pintype "passive"))
      (node (ref "R19") (pin "1") (pinfunction "1_1") (pintype "passive"))
    )
    (net (code "40") (name "Net-(R15-Pad2)") (class "Default")
      (node (ref "R15") (pin "2") (pinfunction "2_2") (pintype "passive"))
      (node (ref "R17") (pin "2") (pinfunction "2_2") (pintype "passive"))
      (node (ref "R18") (pin "1") (pinfunction "1_1") (pintype "passive"))
      (node (ref "R20") (pin "1") (pinfunction "1_1") (pintype "passive"))
    )
    (net (code "41") (name "Net-(R19-Pad2)") (class "Default")
      (node (ref "R19") (pin "2") (pinfunction "2_2") (pintype "passive"))
      (node (ref "R21") (pin "2") (pinfunction "2_2") (pintype "passive"))
      (node (ref "R22") (pin "1") (pinfunction "1_1") (pintype "passive"))
      (node (ref "R24") (pin "1") (pinfunction "1_1") (pintype "passive"))
    )
    (net (code "42") (name "Net-(R20-Pad2)") (class "Default")
      (node (ref "R20") (pin "2") (pinfunction "2_2") (pintype "passive"))
      (node (ref "R22") (pin "2") (pinfunction "2_2") (pintype "passive"))
      (node (ref "R23") (pin "1") (pinfunction "1_1") (pintype "passive"))
      (node (ref "R25") (pin "1") (pinfunction "1_1") (pintype "passive"))
    )
    (net (code "43") (name "Net-(R24-Pad2)") (class "Default")
      (node (ref "R24") (pin "2") (pinfunction "2_2") (pintype "passive"))
      (node (ref "R26") (pin "2") (pinfunction "2_2") (pintype "passive"))
      (node (ref "R27") (pin "1") (pinfunction "1_1") (pintype "passive"))
      (node (ref "R29") (pin "1") (pinfunction "1_1") (pintype "passive"))
    )
    (net (code "44") (name "Net-(R25-Pad2)") (class "Default")
      (node (ref "R25") (pin "2") (pinfunction "2_2") (pintype "passive"))
      (node (ref "R27") (pin "2") (pinfunction "2_2") (pintype "passive"))
      (node (ref "R28") (pin "1") (pinfunction "1_1") (pintype "passive"))
      (node (ref "R30") (pin "1") (pinfunction "1_1") (pintype "passive"))
    )
    (net (code "45") (name "Net-(R29-Pad2)") (class "Default")
      (node (ref "R29") (pin "2") (pinfunction "2_2") (pintype "passive"))
      (node (ref "R31") (pin "2") (pinfunction "2_2") (pintype "passive"))
      (node (ref "R32") (pin "1") (pinfunction "1_1") (pintype "passive"))
      (node (ref "R34") (pin "1") (pinfunction "1_1") (pintype "passive"))
    )
    (net (code "46") (name "Net-(R30-Pad2)") (class "Default")
      (node (ref "R30") (pin "2") (pinfunction "2_2") (pintype "passive"))
      (node (ref "R32") (pin "2") (pinfunction "2_2") (pintype "passive"))
      (node (ref "R33") (pin "1") (pinfunction "1_1") (pintype "passive"))
      (node (ref "R35") (pin "1") (pinfunction "1_1") (pintype "passive"))
    )
    (net (code "47") (name "Net-(R34-Pad2)") (class "Default")
      (node (ref "R34") (pin "2") (pinfunction "2_2") (pintype "passive"))
      (node (ref "R36") (pin "2") (pinfunction "2_2") (pintype "passive"))
      (node (ref "R37") (pin "1") (pinfunction "1_1") (pintype "passive"))
      (node (ref "R39") (pin "1") (pinfunction "1_1") (pintype "passive"))
    )
    (net (code "48") (name "Net-(R35-Pad2)") (class "Default")
      (node (ref "R35") (pin "2") (pinfunction "2_2") (pintype "passive"))
      (node (ref "R37") (pin "2") (pinfunction "2_2") (pintype "passive"))
      (node (ref "R38") (pin "1") (pinfunction "1_1") (pintype "passive"))
      (node (ref "R40") (pin "1") (pinfunction "1_1") (pintype "passive"))
    )
    (net (code "49") (name "Net-(R39-Pad2)") (class "Default")
      (node (ref "R39") (pin "2") (pinfunction "2_2") (pintype "passive"))
      (node (ref "R41") (pin "2") (pinfunction "2_2") (pintype "passive"))
      (node (ref "R42") (pin "1") (pinfunction "1_1") (pintype "passive"))
      (node (ref "R44") (pin "1") (pinfunction "1_1") (pintype "passive"))
    )
    (net (code "50") (name "Net-(R40-Pad2)") (class "Default")
      (node (ref "R40") (pin "2") (pinfunction "2_2") (pintype "passive"))
      (node (ref "R42") (pin "2") (pinfunction "2_2") (pintype "passive"))
      (node (ref "R43") (pin "1") (pinfunction "1_1") (pintype "passive"))
      (node (ref "R45") (pin "1") (pinfunction "1_1") (pintype "passive"))
    )
    (net (code "51") (name "Net-(R44-Pad2)") (class "Default")
      (node (ref "R44") (pin "2") (pinfunction "2_2") (pintype "passive"))
      (node (ref "R47") (pin "2") (pinfunction "2_2") (pintype "passive"))
      (node (ref "R48") (pin "1") (pinfunction "1_1") (pintype "passive"))
      (node (ref "R49") (pin "1") (pinfunction "1_1") (pintype "passive"))
    )
    (net (code "52") (name "Net-(R45-Pad2)") (class "Default")
      (node (ref "R45") (pin "2") (pinfunction "2_2") (pintype "passive"))
      (node (ref "R46") (pin "1") (pinfunction "1_1") (pintype "passive"))
      (node (ref "R48") (pin "2") (pinfunction "2_2") (pintype "passive"))
      (node (ref "R50") (pin "1") (pinfunction "1_1") (pintype "passive"))
    )
    (net (code "53") (name "Net-(R49-Pad2)") (class "Default")
      (node (ref "R49") (pin "2") (pinfunction "2_2") (pintype "passive"))
      (node (ref "R51") (pin "2") (pinfunction "2_2") (pintype "passive"))
      (node (ref "R52") (pin "1") (pinfunction "1_1") (pintype "passive"))
      (node (ref "R54") (pin "1") (pinfunction "1_1") (pintype "passive"))
    )
    (net (code "54") (name "Net-(R50-Pad2)") (class "Default")
      (node (ref "R50") (pin "2") (pinfunction "2_2") (pintype "passive"))
      (node (ref "R52") (pin "2") (pinfunction "2_2") (pintype "passive"))
      (node (ref "R53") (pin "1") (pinfunction "1_1") (pintype "passive"))
      (node (ref "R55") (pin "1") (pinfunction "1_1") (pintype "passive"))
    )
    (net (code "55") (name "Net-(R54-Pad2)") (class "Default")
      (node (ref "R54") (pin "2") (pinfunction "2_2") (pintype "passive"))
      (node (ref "R56") (pin "2") (pinfunction "2_2") (pintype "passive"))
      (node (ref "R57") (pin "1") (pinfunction "1_1") (pintype "passive"))
      (node (ref "R59") (pin "1") (pinfunction "1_1") (pintype "passive"))
    )
    (net (code "56") (name "Net-(R55-Pad2)") (class "Default")
      (node (ref "R55") (pin "2") (pinfunction "2_2") (pintype "passive"))
      (node (ref "R57") (pin "2") (pinfunction "2_2") (pintype "passive"))
      (node (ref "R58") (pin "1") (pinfunction "1_1") (pintype "passive"))
      (node (ref "R60") (pin "1") (pinfunction "1_1") (pintype "passive"))
    )
    (net (code "57") (name "Net-(R59-Pad2)") (class "Default")
      (node (ref "R59") (pin "2") (pinfunction "2_2") (pintype "passive"))
      (node (ref "R61") (pin "2") (pinfunction "2_2") (pintype "passive"))
      (node (ref "R62") (pin "1") (pinfunction "1_1") (pintype "passive"))
      (node (ref "R64") (pin "1") (pinfunction "1_1") (pintype "passive"))
    )
    (net (code "58") (name "Net-(R60-Pad2)") (class "Default")
      (node (ref "R60") (pin "2") (pinfunction "2_2") (pintype "passive"))
      (node (ref "R62") (pin "2") (pinfunction "2_2") (pintype "passive"))
      (node (ref "R63") (pin "1") (pinfunction "1_1") (pintype "passive"))
      (node (ref "R65") (pin "1") (pinfunction "1_1") (pintype "passive"))
    )
    (net (code "59") (name "Net-(R64-Pad2)") (class "Default")
      (node (ref "R64") (pin "2") (pinfunction "2_2") (pintype "passive"))
      (node (ref "R66") (pin "2") (pinfunction "2_2") (pintype "passive"))
      (node (ref "R67") (pin "1") (pinfunction "1_1") (pintype "passive"))
      (node (ref "R69") (pin "1") (pinfunction "1_1") (pintype "passive"))
    )
    (net (code "60") (name "Net-(R65-Pad2)") (class "Default")
      (node (ref "R65") (pin "2") (pinfunction "2_2") (pintype "passive"))
      (node (ref "R67") (pin "2") (pinfunction "2_2") (pintype "passive"))
      (node (ref "R68") (pin "1") (pinfunction "1_1") (pintype "passive"))
      (node (ref "R70") (pin "1") (pinfunction "1_1") (pintype "passive"))
    )
    (net (code "61") (name "Net-(R69-Pad2)") (class "Default")
      (node (ref "R69") (pin "2") (pinfunction "2_2") (pintype "passive"))
      (node (ref "R71") (pin "2") (pinfunction "2_2") (pintype "passive"))
      (node (ref "R72") (pin "1") (pinfunction "1_1") (pintype "passive"))
      (node (ref "R74") (pin "1") (pinfunction "1_1") (pintype "passive"))
    )
    (net (code "62") (name "Net-(R70-Pad2)") (class "Default")
      (node (ref "R70") (pin "2") (pinfunction "2_2") (pintype "passive"))
      (node (ref "R72") (pin "2") (pinfunction "2_2") (pintype "passive"))
      (node (ref "R73") (pin "1") (pinfunction "1_1") (pintype "passive"))
      (node (ref "R75") (pin "1") (pinfunction "1_1") (pintype "passive"))
    )
    (net (code "63") (name "Net-(R74-Pad2)") (class "Default")
      (node (ref "R74") (pin "2") (pinfunction "2_2") (pintype "passive"))
      (node (ref "R76") (pin "2") (pinfunction "2_2") (pintype "passive"))
      (node (ref "R77") (pin "1") (pinfunction "1_1") (pintype "passive"))
      (node (ref "R79") (pin "1") (pinfunction "1_1") (pintype "passive"))
    )
    (net (code "64") (name "Net-(R75-Pad2)") (class "Default")
      (node (ref "R75") (pin "2") (pinfunction "2_2") (pintype "passive"))
      (node (ref "R77") (pin "2") (pinfunction "2_2") (pintype "passive"))
      (node (ref "R78") (pin "1") (pinfunction "1_1") (pintype "passive"))
      (node (ref "R80") (pin "1") (pinfunction "1_1") (pintype "passive"))
    )
    (net (code "65") (name "Net-(R79-Pad2)") (class "Default")
      (node (ref "R79") (pin "2") (pinfunction "2_2") (pintype "passive"))
      (node (ref "R81") (pin "2") (pinfunction "2_2") (pintype "passive"))
      (node (ref "R82") (pin "1") (pinfunction "1_1") (pintype "passive"))
      (node (ref "R84") (pin "1") (pinfunction "1_1") (pintype "passive"))
    )
    (net (code "66") (name "Net-(R80-Pad2)") (class "Default")
      (node (ref "R80") (pin "2") (pinfunction "2_2") (pintype "passive"))
      (node (ref "R82") (pin "2") (pinfunction "2_2") (pintype "passive"))
      (node (ref "R83") (pin "1") (pinfunction "1_1") (pintype "passive"))
      (node (ref "R85") (pin "1") (pinfunction "1_1") (pintype "passive"))
    )
    (net (code "67") (name "Net-(R84-Pad2)") (class "Default")
      (node (ref "R84") (pin "2") (pinfunction "2_2") (pintype "passive"))
      (node (ref "R86") (pin "2") (pinfunction "2_2") (pintype "passive"))
      (node (ref "R87") (pin "1") (pinfunction "1_1") (pintype "passive"))
      (node (ref "R89") (pin "1") (pinfunction "1_1") (pintype "passive"))
    )
    (net (code "68") (name "Net-(R85-Pad2)") (class "Default")
      (node (ref "R85") (pin "2") (pinfunction "2_2") (pintype "passive"))
      (node (ref "R87") (pin "2") (pinfunction "2_2") (pintype "passive"))
      (node (ref "R88") (pin "1") (pinfunction "1_1") (pintype "passive"))
      (node (ref "R90") (pin "1") (pinfunction "1_1") (pintype "passive"))
    )
    (net (code "69") (name "Net-(R89-Pad2)") (class "Default")
      (node (ref "R89") (pin "2") (pinfunction "2_2") (pintype "passive"))
      (node (ref "R91") (pin "2") (pinfunction "2_2") (pintype "passive"))
      (node (ref "R92") (pin "1") (pinfunction "1_1") (pintype "passive"))
      (node (ref "R94") (pin "1") (pinfunction "1_1") (pintype "passive"))
    )
    (net (code "70") (name "Net-(R90-Pad2)") (class "Default")
      (node (ref "R90") (pin "2") (pinfunction "2_2") (pintype "passive"))
      (node (ref "R92") (pin "2") (pinfunction "2_2") (pintype "passive"))
      (node (ref "R93") (pin "1") (pinfunction "1_1") (pintype "passive"))
      (node (ref "R95") (pin "1") (pinfunction "1_1") (pintype "passive"))
    )
    (net (code "71") (name "Net-(R94-Pad2)") (class "Default")
      (node (ref "R94") (pin "2") (pinfunction "2_2") (pintype "passive"))
      (node (ref "R97") (pin "2") (pinfunction "2_2") (pintype "passive"))
      (node (ref "R98") (pin "1") (pinfunction "1_1") (pintype "passive"))
      (node (ref "R99") (pin "1") (pinfunction "1_1") (pintype "passive"))
    )
    (net (code "72") (name "Net-(R100-Pad1)") (class "Default")
      (node (ref "R100") (pin "1") (pinfunction "1_1") (pintype "passive"))
      (node (ref "R95") (pin "2") (pinfunction "2_2") (pintype "passive"))
      (node (ref "R96") (pin "1") (pinfunction "1_1") (pintype "passive"))
      (node (ref "R98") (pin "2") (pinfunction "2_2") (pintype "passive"))
    )
    (net (code "73") (name "Net-(R100-Pad2)") (class "Default")
      (node (ref "R100") (pin "2") (pinfunction "2_2") (pintype "passive"))
      (node (ref "R102") (pin "2") (pinfunction "2_2") (pintype "passive"))
      (node (ref "R103") (pin "1") (pinfunction "1_1") (pintype "passive"))
      (node (ref "R105") (pin "1") (pinfunction "1_1") (pintype "passive"))
    )
    (net (code "74") (name "Net-(R101-Pad2)") (class "Default")
      (node (ref "R101") (pin "2") (pinfunction "2_2") (pintype "passive"))
      (node (ref "R102") (pin "1") (pinfunction "1_1") (pintype "passive"))
      (node (ref "R104") (pin "1") (pinfunction "1_1") (pintype "passive"))
      (node (ref "R99") (pin "2") (pinfunction "2_2") (pintype "passive"))
    )
    (net (code "75") (name "Net-(R104-Pad2)") (class "Default")
      (node (ref "R104") (pin "2") (pinfunction "2_2") (pintype "passive"))
      (node (ref "R106") (pin "2") (pinfunction "2_2") (pintype "passive"))
      (node (ref "R107") (pin "1") (pinfunction "1_1") (pintype "passive"))
      (node (ref "R109") (pin "1") (pinfunction "1_1") (pintype "passive"))
    )
    (net (code "76") (name "Net-(R105-Pad2)") (class "Default")
      (node (ref "R105") (pin "2") (pinfunction "2_2") (pintype "passive"))
      (node (ref "R107") (pin "2") (pinfunction "2_2") (pintype "passive"))
      (node (ref "R108") (pin "1") (pinfunction "1_1") (pintype "passive"))
      (node (ref "R110") (pin "1") (pinfunction "1_1") (pintype "passive"))
    )
    (net (code "77") (name "Net-(R109-Pad2)") (class "Default")
      (node (ref "R109") (pin "2") (pinfunction "2_2") (pintype "passive"))
      (node (ref "R111") (pin "2") (pinfunction "2_2") (pintype "passive"))
      (node (ref "R112") (pin "1") (pinfunction "1_1") (pintype "passive"))
      (node (ref "R114") (pin "1") (pinfunction "1_1") (pintype "passive"))
    )
    (net (code "78") (name "Net-(R110-Pad2)") (class "Default")
      (node (ref "R110") (pin "2") (pinfunction "2_2") (pintype "passive"))
      (node (ref "R112") (pin "2") (pinfunction "2_2") (pintype "passive"))
      (node (ref "R113") (pin "1") (pinfunction "1_1") (pintype "passive"))
      (node (ref "R115") (pin "1") (pinfunction "1_1") (pintype "passive"))
    )
    (net (code "79") (name "Net-(R114-Pad2)") (class "Default")
      (node (ref "R114") (pin "2") (pinfunction "2_2") (pintype "passive"))
      (node (ref "R116") (pin "2") (pinfunction "2_2") (pintype "passive"))
      (node (ref "R117") (pin "1") (pinfunction "1_1") (pintype "passive"))
      (node (ref "R119") (pin "1") (pinfunction "1_1") (pintype "passive"))
    )
    (net (code "80") (name "Net-(R115-Pad2)") (class "Default")
      (node (ref "R115") (pin "2") (pinfunction "2_2") (pintype "passive"))
      (node (ref "R117") (pin "2") (pinfunction "2_2") (pintype "passive"))
      (node (ref "R118") (pin "1") (pinfunction "1_1") (pintype "passive"))
      (node (ref "R120") (pin "1") (pinfunction "1_1") (pintype "passive"))
    )
    (net (code "81") (name "Net-(R119-Pad2)") (class "Default")
      (node (ref "R119") (pin "2") (pinfunction "2_2") (pintype "passive"))
      (node (ref "R121") (pin "2") (pinfunction "2_2") (pintype "passive"))
      (node (ref "R122") (pin "1") (pinfunction "1_1") (pintype "passive"))
      (node (ref "R124") (pin "1") (pinfunction "1_1") (pintype "passive"))
    )
    (net (code "82") (name "Net-(R120-Pad2)") (class "Default")
      (node (ref "R120") (pin "2") (pinfunction "2_2") (pintype "passive"))
      (node (ref "R122") (pin "2") (pinfunction "2_2") (pintype "passive"))
      (node (ref "R123") (pin "1") (pinfunction "1_1") (pintype "passive"))
      (node (ref "R125") (pin "1") (pinfunction "1_1") (pintype "passive"))
    )
    (net (code "83") (name "Net-(R124-Pad2)") (class "Default")
      (node (ref "R124") (pin "2") (pinfunction "2_2") (pintype "passive"))
      (node (ref "R126") (pin "2") (pinfunction "2_2") (pintype "passive"))
      (node (ref "R127") (pin "1") (pinfunction "1_1") (pintype "passive"))
      (node (ref "R129") (pin "1") (pinfunction "1_1") (pintype "passive"))
    )
    (net (code "84") (name "Net-(R125-Pad2)") (class "Default")
      (node (ref "R125") (pin "2") (pinfunction "2_2") (pintype "passive"))
      (node (ref "R127") (pin "2") (pinfunction "2_2") (pintype "passive"))
      (node (ref "R128") (pin "1") (pinfunction "1_1") (pintype "passive"))
      (node (ref "R130") (pin "1") (pinfunction "1_1") (pintype "passive"))
    )
    (net (code "85") (name "Net-(R129-Pad2)") (class "Default")
      (node (ref "R129") (pin "2") (pinfunction "2_2") (pintype "passive"))
      (node (ref "R131") (pin "2") (pinfunction "2_2") (pintype "passive"))
      (node (ref "R132") (pin "1") (pinfunction "1_1") (pintype "passive"))
      (node (ref "R134") (pin "1") (pinfunction "1_1") (pintype "passive"))
    )
    (net (code "86") (name "Net-(R130-Pad2)") (class "Default")
      (node (ref "R130") (pin "2") (pinfunction "2_2") (pintype "passive"))
      (node (ref "R132") (pin "2") (pinfunction "2_2") (pintype "passive"))
      (node (ref "R133") (pin "1") (pinfunction "1_1") (pintype "passive"))
      (node (ref "R135") (pin "1") (pinfunction "1_1") (pintype "passive"))
    )
    (net (code "87") (name "Net-(R134-Pad2)") (class "Default")
      (node (ref "R134") (pin "2") (pinfunction "2_2") (pintype "passive"))
      (node (ref "R136") (pin "2") (pinfunction "2_2") (pintype "passive"))
      (node (ref "R137") (pin "1") (pinfunction "1_1") (pintype "passive"))
      (node (ref "R139") (pin "1") (pinfunction "1_1") (pintype "passive"))
    )
    (net (code "88") (name "Net-(R135-Pad2)") (class "Default")
      (node (ref "R135") (pin "2") (pinfunction "2_2") (pintype "passive"))
      (node (ref "R137") (pin "2") (pinfunction "2_2") (pintype "passive"))
      (node (ref "R138") (pin "1") (pinfunction "1_1") (pintype "passive"))
      (node (ref "R140") (pin "1") (pinfunction "1_1") (pintype "passive"))
    )
    (net (code "89") (name "Net-(R139-Pad2)") (class "Default")
      (node (ref "R139") (pin "2") (pinfunction "2_2") (pintype "passive"))
      (node (ref "R141") (pin "2") (pinfunction "2_2") (pintype "passive"))
      (node (ref "R142") (pin "1") (pinfunction "1_1") (pintype "passive"))
      (node (ref "R144") (pin "1") (pinfunction "1_1") (pintype "passive"))
    )
    (net (code "90") (name "Net-(R140-Pad2)") (class "Default")
      (node (ref "R140") (pin "2") (pinfunction "2_2") (pintype "passive"))
      (node (ref "R142") (pin "2") (pinfunction "2_2") (pintype "passive"))
      (node (ref "R143") (pin "1") (pinfunction "1_1") (pintype "passive"))
      (node (ref "R145") (pin "1") (pinfunction "1_1") (pintype "passive"))
    )
    (net (code "91") (name "Net-(R144-Pad2)") (class "Default")
      (node (ref "R144") (pin "2") (pinfunction "2_2") (pintype "passive"))
      (node (ref "R147") (pin "2") (pinfunction "2_2") (pintype "passive"))
      (node (ref "R148") (pin "1") (pinfunction "1_1") (pintype "passive"))
      (node (ref "R149") (pin "1") (pinfunction "1_1") (pintype "passive"))
    )
    (net (code "92") (name "Net-(R145-Pad2)") (class "Default")
      (node (ref "R145") (pin "2") (pinfunction "2_2") (pintype "passive"))
      (node (ref "R146") (pin "1") (pinfunction "1_1") (pintype "passive"))
      (node (ref "R148") (pin "2") (pinfunction "2_2") (pintype "passive"))
      (node (ref "R150") (pin "1") (pinfunction "1_1") (pintype "passive"))
    )
    (net (code "93") (name "Net-(R149-Pad2)") (class "Default")
      (node (ref "R149") (pin "2") (pinfunction "2_2") (pintype "passive"))
      (node (ref "R151") (pin "2") (pinfunction "2_2") (pintype "passive"))
      (node (ref "R152") (pin "1") (pinfunction "1_1") (pintype "passive"))
      (node (ref "R154") (pin "1") (pinfunction "1_1") (pintype "passive"))
    )
    (net (code "94") (name "Net-(R150-Pad2)") (class "Default")
      (node (ref "R150") (pin "2") (pinfunction "2_2") (pintype "passive"))
      (node (ref "R152") (pin "2") (pinfunction "2_2") (pintype "passive"))
      (node (ref "R153") (pin "1") (pinfunction "1_1") (pintype "passive"))
      (node (ref "R155") (pin "1") (pinfunction "1_1") (pintype "passive"))
    )
    (net (code "95") (name "Net-(R154-Pad2)") (class "Default")
      (node (ref "R154") (pin "2") (pinfunction "2_2") (pintype "passive"))
      (node (ref "R156") (pin "2") (pinfunction "2_2") (pintype "passive"))
      (node (ref "R157") (pin "1") (pinfunction "1_1") (pintype "passive"))
      (node (ref "R159") (pin "1") (pinfunction "1_1") (pintype "passive"))
    )
    (net (code "96") (name "Net-(R155-Pad2)") (class "Default")
      (node (ref "R155") (pin "2") (pinfunction "2_2") (pintype "passive"))
      (node (ref "R157") (pin "2") (pinfunction "2_2") (pintype "passive"))
      (node (ref "R158") (pin "1") (pinfunction "1_1") (pintype "passive"))
      (node (ref "R160") (pin "1") (pinfunction "1_1") (pintype "passive"))
    )
    (net (code "97") (name "Net-(R160-Pad2)") (class "Default")
      (node (ref "R160") (pin "2") (pinfunction "2_2") (pintype "passive"))
      (node (ref "R2") (pin "2") (pinfunction "2_2") (pintype "passive"))
      (node (ref "R3") (pin "1") (pinfunction "1_1") (pintype "passive"))
      (node (ref "R5") (pin "1") (pinfunction "1_1") (pintype "passive"))
    )
    (net (code "98") (name "unconnected-(U$1-PadP1)") (class "Default")
      (node (ref "U$1") (pin "P1") (pinfunction "P1_P1") (pintype "bidirectional"))
    )
    (net (code "99") (name "unconnected-(U$1-PadP2)") (class "Default")
      (node (ref "U$1") (pin "P2") (pinfunction "P2_P2") (pintype "bidirectional"))
    )
    (net (code "100") (name "unconnected-(U$1-PadP35)") (class "Default")
      (node (ref "U$1") (pin "P35") (pinfunction "P35_P35") (pintype "bidirectional"))
    )
    (net (code "101") (name "unconnected-(U$1-PadP36)") (class "Default")
      (node (ref "U$1") (pin "P36") (pinfunction "P36_P36") (pintype "bidirectional"))
    )
    (net (code "102") (name "unconnected-(U$2-PadP$1)") (class "Default")
      (node (ref "U$2") (pin "P$1") (pinfunction "P$1_P$1") (pintype "bidirectional"))
    )
    (net (code "103") (name "unconnected-(U$2-PadP$2)") (class "Default")
      (node (ref "U$2") (pin "P$2") (pinfunction "P$2_P$2") (pintype "bidirectional"))
    )
    (net (code "104") (name "unconnected-(U$2-PadP$19)") (class "Default")
      (node (ref "U$2") (pin "P$19") (pinfunction "P$19_P$19") (pintype "bidirectional"))
    )
    (net (code "105") (name "unconnected-(U$2-PadP$20)") (class "Default")
      (node (ref "U$2") (pin "P$20") (pinfunction "P$20_P$20") (pintype "bidirectional"))
    )
    (net (code "106") (name "unconnected-(U$2-PadP$21)") (class "Default")
      (node (ref "U$2") (pin "P$21") (pinfunction "P$21_P$21") (pintype "bidirectional"))
    )
    (net (code "107") (name "unconnected-(U$2-PadP$22)") (class "Default")
      (node (ref "U$2") (pin "P$22") (pinfunction "P$22_P$22") (pintype "bidirectional"))
    )
    (net (code "108") (name "unconnected-(U$2-PadP$39)") (class "Default")
      (node (ref "U$2") (pin "P$39") (pinfunction "P$39_P$39") (pintype "bidirectional"))
    )
    (net (code "109") (name "unconnected-(U$2-PadP$40)") (class "Default")
      (node (ref "U$2") (pin "P$40") (pinfunction "P$40_P$40") (pintype "bidirectional"))
    )
    (net (code "110") (name "unconnected-(X1-Pad33)") (class "Default")
      (node (ref "X1") (pin "33") (pinfunction "33_33") (pintype "passive"))
    )
    (net (code "111") (name "unconnected-(X1-Pad34)") (class "Default")
      (node (ref "X1") (pin "34") (pinfunction "34_34") (pintype "passive"))
    )
    (net (code "112") (name "unconnected-(X1-Pad35)") (class "Default")
      (node (ref "X1") (pin "35") (pinfunction "35_35") (pintype "passive"))
    )
    (net (code "113") (name "unconnected-(X1-Pad36)") (class "Default")
      (node (ref "X1") (pin "36") (pinfunction "36_36") (pintype "passive"))
    )
    (net (code "114") (name "unconnected-(X1-Pad37)") (class "Default")
      (node (ref "X1") (pin "37") (pinfunction "37_37") (pintype "passive"))
    )
    (net (code "115") (name "unconnected-(X1-PadG1)") (class "Default")
      (node (ref "X1") (pin "G1") (pinfunction "G1_G1") (pintype "passive"))
    )
    (net (code "116") (name "unconnected-(X1-PadG2)") (class "Default")
      (node (ref "X1") (pin "G2") (pinfunction "G2_G2") (pintype "passive"))
    )
  )
)
